# RCShield-v4.net
KiCad netlist of a schematic drawn in EAGLE
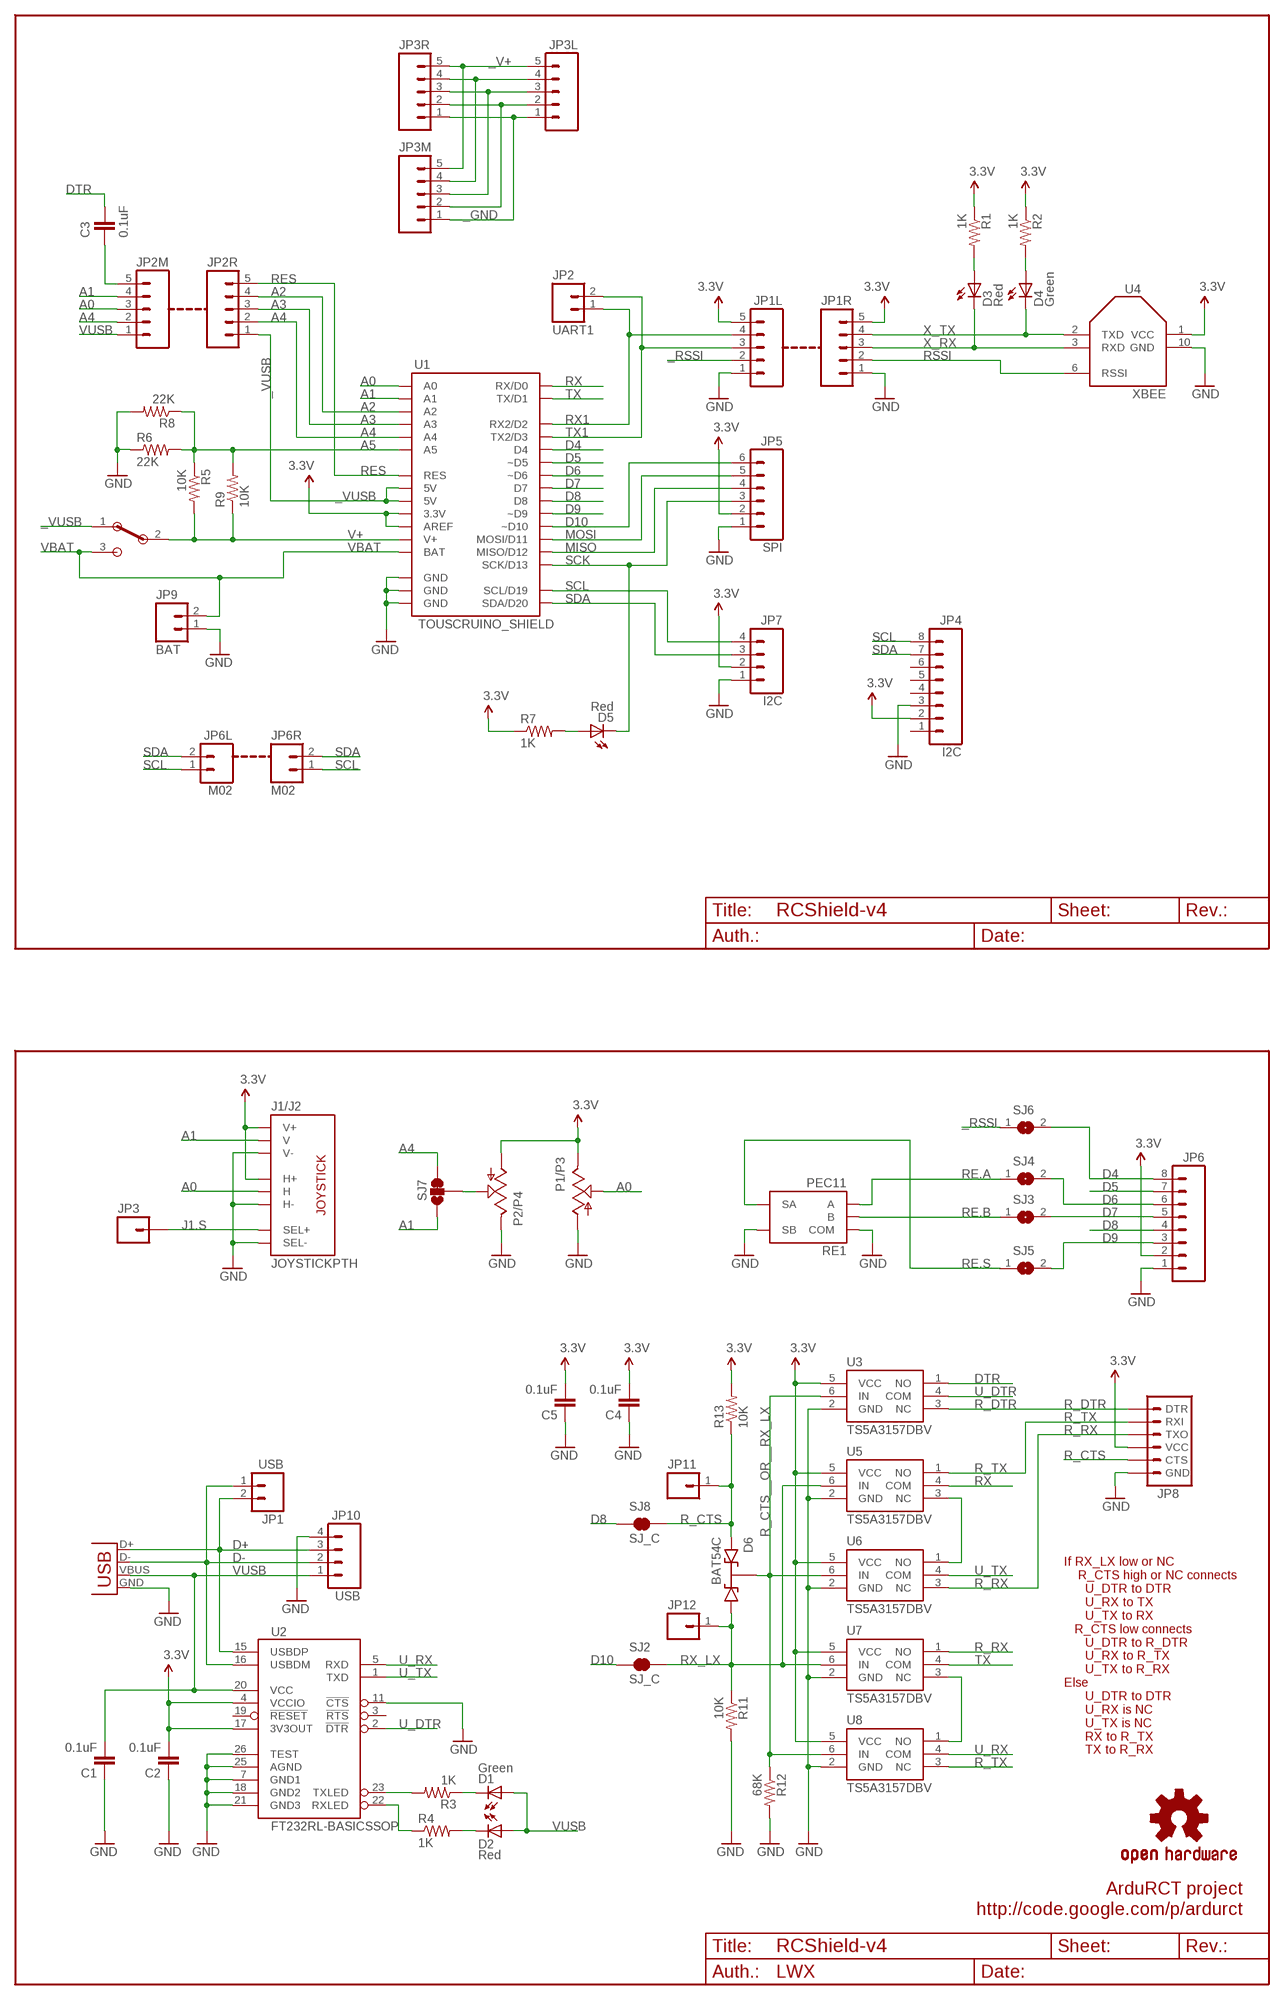
[diagram p0: schematic, sheet 1]

(export (version "E")
  (design (tool "Eeschema 10.0.6"))
  (components
    (comp (ref "C1")
      (value "0.1uF")
      (footprint "eagle-import:0805")
      (libsource (lib "eagle-import") (part "CAP0805"))
    )
    (comp (ref "C2")
      (value "0.1uF")
      (footprint "eagle-import:0805")
      (libsource (lib "eagle-import") (part "CAP0805"))
    )
    (comp (ref "C3")
      (value "0.1uF")
      (footprint "eagle-import:0805")
      (libsource (lib "eagle-import") (part "CAP0805"))
    )
    (comp (ref "C4")
      (value "0.1uF")
      (footprint "eagle-import:0805")
      (libsource (lib "eagle-import") (part "CAP0805"))
    )
    (comp (ref "C5")
      (value "0.1uF")
      (footprint "eagle-import:0805")
      (libsource (lib "eagle-import") (part "CAP0805"))
    )
    (comp (ref "D1")
      (value "Green")
      (footprint "eagle-import:LED")
      (libsource (lib "eagle-import") (part "LED"))
    )
    (comp (ref "D2")
      (value "Red")
      (footprint "eagle-import:LED")
      (libsource (lib "eagle-import") (part "LED"))
    )
    (comp (ref "D3")
      (value "Red")
      (footprint "eagle-import:LED")
      (libsource (lib "eagle-import") (part "LED"))
    )
    (comp (ref "D4")
      (value "Green")
      (footprint "eagle-import:LED")
      (libsource (lib "eagle-import") (part "LED"))
    )
    (comp (ref "D5")
      (value "Red")
      (footprint "eagle-import:LED")
      (libsource (lib "eagle-import") (part "LED"))
    )
    (comp (ref "D6")
      (value "BAT54C")
      (footprint "eagle-import:SOT23-3")
      (libsource (lib "eagle-import") (part "BAT54C"))
    )
    (comp (ref "J1/J2")
      (value "JOYSTICKPTH")
      (footprint "eagle-import:JOYSTICK")
      (libsource (lib "eagle-import") (part "JOYSTICKPTH"))
    )
    (comp (ref "JP1")
      (value "USB")
      (footprint "eagle-import:1X02")
      (libsource (lib "eagle-import") (part "M02"))
    )
    (comp (ref "JP1L")
      (value "M05")
      (footprint "eagle-import:2+3")
      (libsource (lib "eagle-import") (part "M05"))
    )
    (comp (ref "JP1R")
      (value "M05")
      (footprint "eagle-import:2+3")
      (libsource (lib "eagle-import") (part "M05"))
    )
    (comp (ref "JP2")
      (value "UART1")
      (footprint "eagle-import:1X02")
      (libsource (lib "eagle-import") (part "M02"))
    )
    (comp (ref "JP2M")
      (value "M05")
      (footprint "eagle-import:2+3")
      (libsource (lib "eagle-import") (part "M05"))
    )
    (comp (ref "JP2R")
      (value "M05")
      (footprint "eagle-import:2+3")
      (libsource (lib "eagle-import") (part "M05"))
    )
    (comp (ref "JP3")
      (value "M01PTH")
      (footprint "eagle-import:1X01")
      (libsource (lib "eagle-import") (part "M01PTH"))
    )
    (comp (ref "JP3L")
      (value "M05")
      (footprint "eagle-import:2+3")
      (libsource (lib "eagle-import") (part "M05"))
    )
    (comp (ref "JP3M")
      (value "M05")
      (footprint "eagle-import:2+3")
      (libsource (lib "eagle-import") (part "M05"))
    )
    (comp (ref "JP3R")
      (value "M05")
      (footprint "eagle-import:2+3")
      (libsource (lib "eagle-import") (part "M05"))
    )
    (comp (ref "JP4")
      (value "I2C")
      (footprint "eagle-import:1X08")
      (libsource (lib "eagle-import") (part "M08"))
    )
    (comp (ref "JP5")
      (value "SPI")
      (footprint "eagle-import:1X06")
      (libsource (lib "eagle-import") (part "M06SIP"))
    )
    (comp (ref "JP6")
      (value "M08")
      (footprint "eagle-import:1X08")
      (libsource (lib "eagle-import") (part "M08"))
    )
    (comp (ref "JP6L")
      (value "M02")
      (footprint "eagle-import:1X02")
      (libsource (lib "eagle-import") (part "M02"))
    )
    (comp (ref "JP6R")
      (value "M02")
      (footprint "eagle-import:1X02")
      (libsource (lib "eagle-import") (part "M02"))
    )
    (comp (ref "JP7")
      (value "I2C")
      (footprint "eagle-import:1X04")
      (libsource (lib "eagle-import") (part "M04"))
    )
    (comp (ref "JP8")
      (value "ARDUINO_SERIAL_PROGRAM")
      (footprint "eagle-import:1X06_F")
      (libsource (lib "eagle-import") (part "ARDUINO_SERIAL_PROGRAM"))
    )
    (comp (ref "JP9")
      (value "BAT")
      (footprint "eagle-import:1X02")
      (libsource (lib "eagle-import") (part "M02"))
    )
    (comp (ref "JP10")
      (value "USB")
      (footprint "eagle-import:1X04")
      (libsource (lib "eagle-import") (part "M04"))
    )
    (comp (ref "JP11")
      (value "M01SMALL")
      (footprint "eagle-import:1X01_S")
      (libsource (lib "eagle-import") (part "M01SMALL"))
    )
    (comp (ref "JP12")
      (value "M01SMALL")
      (footprint "eagle-import:1X01_S")
      (libsource (lib "eagle-import") (part "M01SMALL"))
    )
    (comp (ref "P1/P3")
      (value "POT")
      (footprint "eagle-import:ALPS_POT")
      (libsource (lib "eagle-import") (part "POT"))
    )
    (comp (ref "P2/P4")
      (value "POT")
      (footprint "eagle-import:ALPS_POT")
      (libsource (lib "eagle-import") (part "POT"))
    )
    (comp (ref "R1")
      (value "1K")
      (footprint "eagle-import:0805")
      (libsource (lib "eagle-import") (part "RESISTOR0805-RES"))
    )
    (comp (ref "R2")
      (value "1K")
      (footprint "eagle-import:0805")
      (libsource (lib "eagle-import") (part "RESISTOR0805-RES"))
    )
    (comp (ref "R3")
      (value "1K")
      (footprint "eagle-import:0805")
      (libsource (lib "eagle-import") (part "RESISTOR0805-RES"))
    )
    (comp (ref "R4")
      (value "1K")
      (footprint "eagle-import:0805")
      (libsource (lib "eagle-import") (part "RESISTOR0805-RES"))
    )
    (comp (ref "R5")
      (value "10K")
      (footprint "eagle-import:0805")
      (libsource (lib "eagle-import") (part "RESISTOR0805-RES"))
    )
    (comp (ref "R6")
      (value "22K")
      (footprint "eagle-import:0805")
      (libsource (lib "eagle-import") (part "RESISTOR0805-RES"))
    )
    (comp (ref "R7")
      (value "1K")
      (footprint "eagle-import:0805")
      (libsource (lib "eagle-import") (part "RESISTOR0805-RES"))
    )
    (comp (ref "R8")
      (value "22K")
      (footprint "eagle-import:0207_7")
      (libsource (lib "eagle-import") (part "R-US_0207/7"))
    )
    (comp (ref "R9")
      (value "10K")
      (footprint "eagle-import:0207_7")
      (libsource (lib "eagle-import") (part "R-US_0207/7"))
    )
    (comp (ref "R11")
      (value "10K")
      (footprint "eagle-import:0805")
      (libsource (lib "eagle-import") (part "RESISTOR0805-RES"))
    )
    (comp (ref "R12")
      (value "68K")
      (footprint "eagle-import:0805")
      (libsource (lib "eagle-import") (part "RESISTOR0805-RES"))
    )
    (comp (ref "R13")
      (value "10K")
      (footprint "eagle-import:0805")
      (libsource (lib "eagle-import") (part "RESISTOR0805-RES"))
    )
    (comp (ref "RE1")
      (value "PEC11")
      (footprint "eagle-import:PEC11")
      (libsource (lib "eagle-import") (part "PEC11"))
    )
    (comp (ref "S4")
      (value "EG1224")
      (footprint "eagle-import:EG1224")
      (libsource (lib "eagle-import") (part "EG1224"))
    )
    (comp (ref "SJ2")
      (value "SJ_C")
      (footprint "eagle-import:SJ_C")
      (libsource (lib "eagle-import") (part "SJ_C"))
    )
    (comp (ref "SJ3") (value "SJ") (footprint "eagle-import:SJ") (libsource (lib "eagle-import") (part "SJ")))
    (comp (ref "SJ4") (value "SJ") (footprint "eagle-import:SJ") (libsource (lib "eagle-import") (part "SJ")))
    (comp (ref "SJ5") (value "SJ") (footprint "eagle-import:SJ") (libsource (lib "eagle-import") (part "SJ")))
    (comp (ref "SJ6") (value "SJ") (footprint "eagle-import:SJ") (libsource (lib "eagle-import") (part "SJ")))
    (comp (ref "SJ7")
      (value "SJ_2WAYS_1-2W")
      (footprint "eagle-import:SJ_2WAYS_1-2")
      (libsource (lib "eagle-import") (part "SJ_2WAYS_1-2W"))
    )
    (comp (ref "SJ8")
      (value "SJ_C")
      (footprint "eagle-import:SJ_C")
      (libsource (lib "eagle-import") (part "SJ_C"))
    )
    (comp (ref "U$1")
      (value "OSHW-LOGOM")
      (footprint "eagle-import:OSHW-LOGO-M")
      (libsource (lib "eagle-import") (part "OSHW-LOGOM"))
    )
    (comp (ref "U1")
      (value "TOUSCRUINO_SHIELD")
      (footprint "eagle-import:TOUSCRUINO_SHIELD_SPLIT")
      (libsource (lib "eagle-import") (part "TOUSCRUINO_SHIELDSPLIT"))
    )
    (comp (ref "U2")
      (value "FT232RL-BASICSSOP")
      (footprint "eagle-import:SSOP28DB")
      (libsource (lib "eagle-import") (part "FT232RL-BASICSSOP"))
    )
    (comp (ref "U3")
      (value "TS5A3157DBV")
      (footprint "eagle-import:SOT23-6")
      (libsource (lib "eagle-import") (part "TS5A3157DBV"))
    )
    (comp (ref "U4")
      (value "XBEE")
      (footprint "eagle-import:XBEE-SMD")
      (libsource (lib "eagle-import") (part "XBEE-RSSI"))
    )
    (comp (ref "U5")
      (value "TS5A3157DBV")
      (footprint "eagle-import:SOT23-6")
      (libsource (lib "eagle-import") (part "TS5A3157DBV"))
    )
    (comp (ref "U6")
      (value "TS5A3157DBV")
      (footprint "eagle-import:SOT23-6")
      (libsource (lib "eagle-import") (part "TS5A3157DBV"))
    )
    (comp (ref "U7")
      (value "TS5A3157DBV")
      (footprint "eagle-import:SOT23-6")
      (libsource (lib "eagle-import") (part "TS5A3157DBV"))
    )
    (comp (ref "U8")
      (value "TS5A3157DBV")
      (footprint "eagle-import:SOT23-6")
      (libsource (lib "eagle-import") (part "TS5A3157DBV"))
    )
    (comp (ref "X1")
      (value "USB")
      (footprint "eagle-import:USB-MICROB")
      (libsource (lib "eagle-import") (part "USB"))
    )
  )
  (nets
    (net (code "1") (name "/A0") (class "Default")
      (node (ref "J1/J2") (pin "H2") (pinfunction "H_H2") (pintype "bidirectional"))
      (node (ref "JP2M") (pin "3") (pinfunction "3_3") (pintype "passive"))
      (node (ref "P1/P3") (pin "P$2") (pinfunction "S_P$2") (pintype "passive"))
      (node (ref "U1") (pin "A0") (pinfunction "A0_A0") (pintype "bidirectional"))
    )
    (net (code "2") (name "/A1") (class "Default")
      (node (ref "J1/J2") (pin "V2") (pinfunction "V_V2") (pintype "bidirectional"))
      (node (ref "JP2M") (pin "4") (pinfunction "4_4") (pintype "passive"))
      (node (ref "SJ7") (pin "3") (pinfunction "3_3") (pintype "passive"))
      (node (ref "U1") (pin "A1") (pinfunction "A1_A1") (pintype "bidirectional"))
    )
    (net (code "3") (name "/A2") (class "Default")
      (node (ref "JP2R") (pin "4") (pinfunction "4_4") (pintype "passive"))
      (node (ref "U1") (pin "A2") (pinfunction "A2_A2") (pintype "bidirectional"))
    )
    (net (code "4") (name "/A3") (class "Default")
      (node (ref "JP2R") (pin "3") (pinfunction "3_3") (pintype "passive"))
      (node (ref "U1") (pin "A3") (pinfunction "A3_A3") (pintype "bidirectional"))
    )
    (net (code "5") (name "/A4") (class "Default")
      (node (ref "JP2M") (pin "2") (pinfunction "2_2") (pintype "passive"))
      (node (ref "JP2R") (pin "2") (pinfunction "2_2") (pintype "passive"))
      (node (ref "SJ7") (pin "1") (pinfunction "1_1") (pintype "passive"))
      (node (ref "U1") (pin "A4") (pinfunction "A4_A4") (pintype "bidirectional"))
    )
    (net (code "6") (name "/A5") (class "Default")
      (node (ref "R5") (pin "1") (pinfunction "1_1") (pintype "passive"))
      (node (ref "R6") (pin "2") (pinfunction "2_2") (pintype "passive"))
      (node (ref "R8") (pin "1") (pinfunction "1_1") (pintype "passive"))
      (node (ref "R9") (pin "2") (pinfunction "2_2") (pintype "passive"))
      (node (ref "U1") (pin "A5") (pinfunction "A5_A5") (pintype "bidirectional"))
    )
    (net (code "7") (name "/D+") (class "Default")
      (node (ref "JP1") (pin "2") (pinfunction "2_2") (pintype "passive"))
      (node (ref "JP10") (pin "3") (pinfunction "3_3") (pintype "passive"))
      (node (ref "U2") (pin "15") (pinfunction "USBDP_15") (pintype "bidirectional"))
      (node (ref "X1") (pin "D+") (pinfunction "D+_D+") (pintype "bidirectional"))
    )
    (net (code "8") (name "/D-") (class "Default")
      (node (ref "JP1") (pin "1") (pinfunction "1_1") (pintype "passive"))
      (node (ref "JP10") (pin "2") (pinfunction "2_2") (pintype "passive"))
      (node (ref "U2") (pin "16") (pinfunction "USBDM_16") (pintype "bidirectional"))
      (node (ref "X1") (pin "D-") (pinfunction "D-_D-") (pintype "bidirectional"))
    )
    (net (code "9") (name "/D4") (class "Default")
      (node (ref "JP6") (pin "8") (pinfunction "8_8") (pintype "passive"))
      (node (ref "SJ6") (pin "2") (pinfunction "2_2") (pintype "passive"))
      (node (ref "U1") (pin "D4") (pinfunction "D4_D4") (pintype "bidirectional"))
    )
    (net (code "10") (name "/D5") (class "Default")
      (node (ref "JP6") (pin "7") (pinfunction "7_7") (pintype "passive"))
      (node (ref "U1") (pin "D5") (pinfunction "~{D5}_D5") (pintype "bidirectional"))
    )
    (net (code "11") (name "/D6") (class "Default")
      (node (ref "JP6") (pin "6") (pinfunction "6_6") (pintype "passive"))
      (node (ref "SJ4") (pin "2") (pinfunction "2_2") (pintype "passive"))
      (node (ref "U1") (pin "D6") (pinfunction "~{D6}_D6") (pintype "bidirectional"))
    )
    (net (code "12") (name "/D7") (class "Default")
      (node (ref "JP6") (pin "5") (pinfunction "5_5") (pintype "passive"))
      (node (ref "SJ3") (pin "2") (pinfunction "2_2") (pintype "passive"))
      (node (ref "U1") (pin "D7") (pinfunction "D7_D7") (pintype "bidirectional"))
    )
    (net (code "13") (name "/D8") (class "Default")
      (node (ref "JP6") (pin "4") (pinfunction "4_4") (pintype "passive"))
      (node (ref "SJ8") (pin "1") (pinfunction "1_1") (pintype "passive"))
      (node (ref "U1") (pin "D8") (pinfunction "D8_D8") (pintype "bidirectional"))
    )
    (net (code "14") (name "/D9") (class "Default")
      (node (ref "JP6") (pin "3") (pinfunction "3_3") (pintype "passive"))
      (node (ref "SJ5") (pin "2") (pinfunction "2_2") (pintype "passive"))
      (node (ref "U1") (pin "D9") (pinfunction "~{D9}_D9") (pintype "bidirectional"))
    )
    (net (code "15") (name "/D10") (class "Default")
      (node (ref "JP5") (pin "6") (pinfunction "6_6") (pintype "passive"))
      (node (ref "SJ2") (pin "1") (pinfunction "1_1") (pintype "passive"))
      (node (ref "U1") (pin "D10") (pinfunction "~{D10}_D10") (pintype "bidirectional"))
    )
    (net (code "16") (name "/DTR") (class "Default")
      (node (ref "C3") (pin "1") (pinfunction "1_1") (pintype "passive"))
      (node (ref "U3") (pin "1") (pinfunction "NO_1") (pintype "bidirectional"))
    )
    (net (code "17") (name "/J1.S") (class "Default")
      (node (ref "J1/J2") (pin "B1A") (pinfunction "SEL+_B1A") (pintype "bidirectional"))
      (node (ref "JP3") (pin "1") (pinfunction "1_1") (pintype "passive"))
    )
    (net (code "18") (name "/MISO") (class "Default")
      (node (ref "JP5") (pin "4") (pinfunction "4_4") (pintype "passive"))
      (node (ref "U1") (pin "D12") (pinfunction "MISO/D12_D12") (pintype "bidirectional"))
    )
    (net (code "19") (name "/MOSI") (class "Default")
      (node (ref "JP5") (pin "5") (pinfunction "5_5") (pintype "passive"))
      (node (ref "U1") (pin "D11") (pinfunction "MOSI/D11_D11") (pintype "bidirectional"))
    )
    (net (code "20") (name "/RE.A") (class "Default")
      (node (ref "RE1") (pin "A") (pinfunction "A_A") (pintype "bidirectional"))
      (node (ref "SJ4") (pin "1") (pinfunction "1_1") (pintype "passive"))
    )
    (net (code "21") (name "/RE.B") (class "Default")
      (node (ref "RE1") (pin "B") (pinfunction "B_B") (pintype "bidirectional"))
      (node (ref "SJ3") (pin "1") (pinfunction "1_1") (pintype "passive"))
    )
    (net (code "22") (name "/RE.S") (class "Default")
      (node (ref "RE1") (pin "S1") (pinfunction "SA_S1") (pintype "bidirectional"))
      (node (ref "SJ5") (pin "1") (pinfunction "1_1") (pintype "passive"))
    )
    (net (code "23") (name "/RES") (class "Default")
      (node (ref "JP2R") (pin "5") (pinfunction "5_5") (pintype "passive"))
      (node (ref "U1") (pin "RES") (pinfunction "RES_RES") (pintype "bidirectional"))
    )
    (net (code "24") (name "/RSSI") (class "Default")
      (node (ref "JP1R") (pin "2") (pinfunction "2_2") (pintype "passive"))
      (node (ref "U4") (pin "6") (pinfunction "RSSI_6") (pintype "bidirectional"))
    )
    (net (code "25") (name "/RX") (class "Default")
      (node (ref "U1") (pin "RX") (pinfunction "RX/D0_RX") (pintype "bidirectional"))
      (node (ref "U5") (pin "4") (pinfunction "COM_4") (pintype "bidirectional"))
    )
    (net (code "26") (name "/RX1") (class "Default")
      (node (ref "JP1L") (pin "4") (pinfunction "4_4") (pintype "passive"))
      (node (ref "JP2") (pin "1") (pinfunction "1_1") (pintype "passive"))
      (node (ref "U1") (pin "D2") (pinfunction "RX2/D2_D2") (pintype "bidirectional"))
    )
    (net (code "27") (name "/RX_LX") (class "Default")
      (node (ref "D6") (pin "1") (pinfunction "A1_1") (pintype "bidirectional"))
      (node (ref "JP12") (pin "1") (pinfunction "1_1") (pintype "passive"))
      (node (ref "R11") (pin "1") (pinfunction "1_1") (pintype "passive"))
      (node (ref "SJ2") (pin "2") (pinfunction "2_2") (pintype "passive"))
      (node (ref "U5") (pin "6") (pinfunction "IN_6") (pintype "bidirectional"))
      (node (ref "U7") (pin "6") (pinfunction "IN_6") (pintype "bidirectional"))
    )
    (net (code "28") (name "/R_CTS") (class "Default")
      (node (ref "D6") (pin "2") (pinfunction "A2_2") (pintype "bidirectional"))
      (node (ref "JP11") (pin "1") (pinfunction "1_1") (pintype "passive"))
      (node (ref "JP8") (pin "5") (pinfunction "CTS_5") (pintype "passive"))
      (node (ref "R13") (pin "1") (pinfunction "1_1") (pintype "passive"))
      (node (ref "SJ8") (pin "2") (pinfunction "2_2") (pintype "passive"))
    )
    (net (code "29") (name "/R_CTS__OR__RX_LX") (class "Default")
      (node (ref "D6") (pin "3") (pinfunction "K_3") (pintype "bidirectional"))
      (node (ref "R12") (pin "1") (pinfunction "1_1") (pintype "passive"))
      (node (ref "U3") (pin "6") (pinfunction "IN_6") (pintype "bidirectional"))
      (node (ref "U6") (pin "6") (pinfunction "IN_6") (pintype "bidirectional"))
      (node (ref "U8") (pin "6") (pinfunction "IN_6") (pintype "bidirectional"))
    )
    (net (code "30") (name "/R_DTR") (class "Default")
      (node (ref "JP8") (pin "1") (pinfunction "DTR_1") (pintype "passive"))
      (node (ref "U3") (pin "3") (pinfunction "NC_3") (pintype "bidirectional"))
    )
    (net (code "31") (name "/R_RX") (class "Default")
      (node (ref "JP8") (pin "3") (pinfunction "TXO_3") (pintype "passive"))
      (node (ref "U6") (pin "3") (pinfunction "NC_3") (pintype "bidirectional"))
      (node (ref "U7") (pin "1") (pinfunction "NO_1") (pintype "bidirectional"))
    )
    (net (code "32") (name "/R_TX") (class "Default")
      (node (ref "JP8") (pin "2") (pinfunction "RXI_2") (pintype "passive"))
      (node (ref "U5") (pin "1") (pinfunction "NO_1") (pintype "bidirectional"))
      (node (ref "U8") (pin "3") (pinfunction "NC_3") (pintype "bidirectional"))
    )
    (net (code "33") (name "/SCK") (class "Default")
      (node (ref "D5") (pin "C1") (pinfunction "C_C1") (pintype "passive"))
      (node (ref "JP5") (pin "3") (pinfunction "3_3") (pintype "passive"))
      (node (ref "U1") (pin "D13") (pinfunction "SCK/D13_D13") (pintype "bidirectional"))
    )
    (net (code "34") (name "/SCL") (class "Default")
      (node (ref "JP4") (pin "8") (pinfunction "8_8") (pintype "passive"))
      (node (ref "JP6L") (pin "1") (pinfunction "1_1") (pintype "passive"))
      (node (ref "JP6R") (pin "1") (pinfunction "1_1") (pintype "passive"))
      (node (ref "JP7") (pin "4") (pinfunction "4_4") (pintype "passive"))
      (node (ref "U1") (pin "SCL") (pinfunction "SCL/D19_SCL") (pintype "bidirectional"))
    )
    (net (code "35") (name "/SDA") (class "Default")
      (node (ref "JP4") (pin "7") (pinfunction "7_7") (pintype "passive"))
      (node (ref "JP6L") (pin "2") (pinfunction "2_2") (pintype "passive"))
      (node (ref "JP6R") (pin "2") (pinfunction "2_2") (pintype "passive"))
      (node (ref "JP7") (pin "3") (pinfunction "3_3") (pintype "passive"))
      (node (ref "U1") (pin "SDA") (pinfunction "SDA/D20_SDA") (pintype "bidirectional"))
    )
    (net (code "36") (name "/TX") (class "Default")
      (node (ref "U1") (pin "TX") (pinfunction "TX/D1_TX") (pintype "bidirectional"))
      (node (ref "U7") (pin "4") (pinfunction "COM_4") (pintype "bidirectional"))
    )
    (net (code "37") (name "/TX1") (class "Default")
      (node (ref "JP1L") (pin "3") (pinfunction "3_3") (pintype "passive"))
      (node (ref "JP2") (pin "2") (pinfunction "2_2") (pintype "passive"))
      (node (ref "U1") (pin "D3") (pinfunction "TX2/D3_D3") (pintype "bidirectional"))
    )
    (net (code "38") (name "/U_DTR") (class "Default")
      (node (ref "U2") (pin "2") (pinfunction "~{DTR}_2") (pintype "bidirectional"))
      (node (ref "U3") (pin "4") (pinfunction "COM_4") (pintype "bidirectional"))
    )
    (net (code "39") (name "/U_RX") (class "Default")
      (node (ref "U2") (pin "5") (pinfunction "RXD_5") (pintype "input"))
      (node (ref "U8") (pin "4") (pinfunction "COM_4") (pintype "bidirectional"))
    )
    (net (code "40") (name "/U_TX") (class "Default")
      (node (ref "U2") (pin "1") (pinfunction "TXD_1") (pintype "output"))
      (node (ref "U6") (pin "4") (pinfunction "COM_4") (pintype "bidirectional"))
    )
    (net (code "41") (name "/V+") (class "Default")
      (node (ref "R5") (pin "2") (pinfunction "2_2") (pintype "passive"))
      (node (ref "R9") (pin "1") (pinfunction "1_1") (pintype "passive"))
      (node (ref "S4") (pin "2") (pinfunction "2_2") (pintype "bidirectional"))
      (node (ref "U1") (pin "V+") (pinfunction "V+_V+") (pintype "bidirectional"))
    )
    (net (code "42") (name "/VBAT") (class "Default")
      (node (ref "JP9") (pin "2") (pinfunction "2_2") (pintype "passive"))
      (node (ref "S4") (pin "3") (pinfunction "3_3") (pintype "bidirectional"))
      (node (ref "U1") (pin "BAT") (pinfunction "BAT_BAT") (pintype "bidirectional"))
    )
    (net (code "43") (name "/VUSB") (class "Default")
      (node (ref "C1") (pin "2") (pinfunction "2_2") (pintype "passive"))
      (node (ref "D1") (pin "A1") (pinfunction "A_A1") (pintype "passive"))
      (node (ref "D2") (pin "A1") (pinfunction "A_A1") (pintype "passive"))
      (node (ref "JP10") (pin "1") (pinfunction "1_1") (pintype "passive"))
      (node (ref "JP2M") (pin "1") (pinfunction "1_1") (pintype "passive"))
      (node (ref "U2") (pin "20") (pinfunction "VCC_20") (pintype "bidirectional"))
      (node (ref "X1") (pin "VBUS") (pinfunction "VBUS_VBUS") (pintype "bidirectional"))
    )
    (net (code "44") (name "/X_RX") (class "Default")
      (node (ref "D3") (pin "C1") (pinfunction "C_C1") (pintype "passive"))
      (node (ref "JP1R") (pin "3") (pinfunction "3_3") (pintype "passive"))
      (node (ref "U4") (pin "3") (pinfunction "RXD_3") (pintype "bidirectional"))
    )
    (net (code "45") (name "/X_TX") (class "Default")
      (node (ref "D4") (pin "C1") (pinfunction "C_C1") (pintype "passive"))
      (node (ref "JP1R") (pin "4") (pinfunction "4_4") (pintype "passive"))
      (node (ref "U4") (pin "2") (pinfunction "TXD_2") (pintype "bidirectional"))
    )
    (net (code "46") (name "/_GND") (class "Default")
      (node (ref "JP3L") (pin "1") (pinfunction "1_1") (pintype "passive"))
      (node (ref "JP3M") (pin "1") (pinfunction "1_1") (pintype "passive"))
      (node (ref "JP3R") (pin "1") (pinfunction "1_1") (pintype "passive"))
    )
    (net (code "47") (name "/_RSSI") (class "Default")
      (node (ref "JP1L") (pin "2") (pinfunction "2_2") (pintype "passive"))
      (node (ref "SJ6") (pin "1") (pinfunction "1_1") (pintype "passive"))
    )
    (net (code "48") (name "/_V+") (class "Default")
      (node (ref "JP3L") (pin "5") (pinfunction "5_5") (pintype "passive"))
      (node (ref "JP3M") (pin "5") (pinfunction "5_5") (pintype "passive"))
      (node (ref "JP3R") (pin "5") (pinfunction "5_5") (pintype "passive"))
    )
    (net (code "49") (name "/_VUSB") (class "Default")
      (node (ref "JP2R") (pin "1") (pinfunction "1_1") (pintype "passive"))
      (node (ref "S4") (pin "1") (pinfunction "1_1") (pintype "bidirectional"))
      (node (ref "U1") (pin "5V@0") (pinfunction "5V_5V@0") (pintype "bidirectional"))
      (node (ref "U1") (pin "5V@1") (pinfunction "5V_5V@1") (pintype "bidirectional"))
    )
    (net (code "50") (name "3.3V") (class "Default")
      (node (ref "C2") (pin "2") (pinfunction "2_2") (pintype "passive"))
      (node (ref "C4") (pin "2") (pinfunction "2_2") (pintype "passive"))
      (node (ref "C5") (pin "2") (pinfunction "2_2") (pintype "passive"))
      (node (ref "J1/J2") (pin "H1") (pinfunction "H+_H1") (pintype "bidirectional"))
      (node (ref "J1/J2") (pin "V1") (pinfunction "V+_V1") (pintype "bidirectional"))
      (node (ref "JP1L") (pin "5") (pinfunction "5_5") (pintype "passive"))
      (node (ref "JP1R") (pin "5") (pinfunction "5_5") (pintype "passive"))
      (node (ref "JP4") (pin "2") (pinfunction "2_2") (pintype "passive"))
      (node (ref "JP5") (pin "2") (pinfunction "2_2") (pintype "passive"))
      (node (ref "JP6") (pin "2") (pinfunction "2_2") (pintype "passive"))
      (node (ref "JP7") (pin "2") (pinfunction "2_2") (pintype "passive"))
      (node (ref "JP8") (pin "4") (pinfunction "VCC_4") (pintype "passive"))
      (node (ref "P1/P3") (pin "P$1") (pinfunction "E_P$1") (pintype "passive"))
      (node (ref "P2/P4") (pin "P$3") (pinfunction "A_P$3") (pintype "passive"))
      (node (ref "R1") (pin "1") (pinfunction "1_1") (pintype "passive"))
      (node (ref "R13") (pin "2") (pinfunction "2_2") (pintype "passive"))
      (node (ref "R2") (pin "1") (pinfunction "1_1") (pintype "passive"))
      (node (ref "R7") (pin "1") (pinfunction "1_1") (pintype "passive"))
      (node (ref "U1") (pin "3.3V") (pinfunction "3.3V_3.3V") (pintype "bidirectional"))
      (node (ref "U1") (pin "AREF") (pinfunction "AREF_AREF") (pintype "bidirectional"))
      (node (ref "U2") (pin "17") (pinfunction "3V3OUT_17") (pintype "output"))
      (node (ref "U2") (pin "4") (pinfunction "VCCIO_4") (pintype "bidirectional"))
      (node (ref "U3") (pin "5") (pinfunction "VCC_5") (pintype "bidirectional"))
      (node (ref "U4") (pin "1") (pinfunction "VCC_1") (pintype "bidirectional"))
      (node (ref "U5") (pin "5") (pinfunction "VCC_5") (pintype "bidirectional"))
      (node (ref "U6") (pin "5") (pinfunction "VCC_5") (pintype "bidirectional"))
      (node (ref "U7") (pin "5") (pinfunction "VCC_5") (pintype "bidirectional"))
      (node (ref "U8") (pin "5") (pinfunction "VCC_5") (pintype "bidirectional"))
    )
    (net (code "51") (name "GND") (class "Default")
      (node (ref "C1") (pin "1") (pinfunction "1_1") (pintype "passive"))
      (node (ref "C2") (pin "1") (pinfunction "1_1") (pintype "passive"))
      (node (ref "C4") (pin "1") (pinfunction "1_1") (pintype "passive"))
      (node (ref "C5") (pin "1") (pinfunction "1_1") (pintype "passive"))
      (node (ref "J1/J2") (pin "B2A") (pinfunction "SEL-_B2A") (pintype "bidirectional"))
      (node (ref "J1/J2") (pin "H3") (pinfunction "H-_H3") (pintype "bidirectional"))
      (node (ref "J1/J2") (pin "V3") (pinfunction "V-_V3") (pintype "bidirectional"))
      (node (ref "JP10") (pin "4") (pinfunction "4_4") (pintype "passive"))
      (node (ref "JP1L") (pin "1") (pinfunction "1_1") (pintype "passive"))
      (node (ref "JP1R") (pin "1") (pinfunction "1_1") (pintype "passive"))
      (node (ref "JP4") (pin "3") (pinfunction "3_3") (pintype "passive"))
      (node (ref "JP5") (pin "1") (pinfunction "1_1") (pintype "passive"))
      (node (ref "JP6") (pin "1") (pinfunction "1_1") (pintype "passive"))
      (node (ref "JP7") (pin "1") (pinfunction "1_1") (pintype "passive"))
      (node (ref "JP8") (pin "6") (pinfunction "GND_6") (pintype "passive"))
      (node (ref "JP9") (pin "1") (pinfunction "1_1") (pintype "passive"))
      (node (ref "P1/P3") (pin "P$3") (pinfunction "A_P$3") (pintype "passive"))
      (node (ref "P2/P4") (pin "P$1") (pinfunction "E_P$1") (pintype "passive"))
      (node (ref "R11") (pin "2") (pinfunction "2_2") (pintype "passive"))
      (node (ref "R12") (pin "2") (pinfunction "2_2") (pintype "passive"))
      (node (ref "R6") (pin "1") (pinfunction "1_1") (pintype "passive"))
      (node (ref "R8") (pin "2") (pinfunction "2_2") (pintype "passive"))
      (node (ref "RE1") (pin "C") (pinfunction "COM_C") (pintype "bidirectional"))
      (node (ref "RE1") (pin "S2") (pinfunction "SB_S2") (pintype "bidirectional"))
      (node (ref "U1") (pin "GND@0") (pinfunction "GND_GND@0") (pintype "bidirectional"))
      (node (ref "U1") (pin "GND@1") (pinfunction "GND_GND@1") (pintype "bidirectional"))
      (node (ref "U1") (pin "GND@2") (pinfunction "GND_GND@2") (pintype "bidirectional"))
      (node (ref "U2") (pin "11") (pinfunction "~{CTS}_11") (pintype "bidirectional"))
      (node (ref "U2") (pin "18") (pinfunction "GND2_18") (pintype "bidirectional"))
      (node (ref "U2") (pin "21") (pinfunction "GND3_21") (pintype "bidirectional"))
      (node (ref "U2") (pin "25") (pinfunction "AGND_25") (pintype "bidirectional"))
      (node (ref "U2") (pin "26") (pinfunction "TEST_26") (pintype "input"))
      (node (ref "U2") (pin "7") (pinfunction "GND1_7") (pintype "bidirectional"))
      (node (ref "U3") (pin "2") (pinfunction "GND_2") (pintype "bidirectional"))
      (node (ref "U4") (pin "10") (pinfunction "GND_10") (pintype "bidirectional"))
      (node (ref "U5") (pin "2") (pinfunction "GND_2") (pintype "bidirectional"))
      (node (ref "U6") (pin "2") (pinfunction "GND_2") (pintype "bidirectional"))
      (node (ref "U7") (pin "2") (pinfunction "GND_2") (pintype "bidirectional"))
      (node (ref "U8") (pin "2") (pinfunction "GND_2") (pintype "bidirectional"))
      (node (ref "X1") (pin "GND") (pinfunction "GND_GND") (pintype "bidirectional"))
    )
    (net (code "52") (name "Net-(C3-Pad2)") (class "Default")
      (node (ref "C3") (pin "2") (pinfunction "2_2") (pintype "passive"))
      (node (ref "JP2M") (pin "5") (pinfunction "5_5") (pintype "passive"))
    )
    (net (code "53") (name "Net-(D1-C)") (class "Default")
      (node (ref "D1") (pin "C1") (pinfunction "C_C1") (pintype "passive"))
      (node (ref "R3") (pin "1") (pinfunction "1_1") (pintype "passive"))
    )
    (net (code "54") (name "Net-(D2-C)") (class "Default")
      (node (ref "D2") (pin "C1") (pinfunction "C_C1") (pintype "passive"))
      (node (ref "R4") (pin "2") (pinfunction "2_2") (pintype "passive"))
    )
    (net (code "55") (name "Net-(D3-A)") (class "Default")
      (node (ref "D3") (pin "A1") (pinfunction "A_A1") (pintype "passive"))
      (node (ref "R1") (pin "2") (pinfunction "2_2") (pintype "passive"))
    )
    (net (code "56") (name "Net-(D4-A)") (class "Default")
      (node (ref "D4") (pin "A1") (pinfunction "A_A1") (pintype "passive"))
      (node (ref "R2") (pin "2") (pinfunction "2_2") (pintype "passive"))
    )
    (net (code "57") (name "Net-(D5-A)") (class "Default")
      (node (ref "D5") (pin "A1") (pinfunction "A_A1") (pintype "passive"))
      (node (ref "R7") (pin "2") (pinfunction "2_2") (pintype "passive"))
    )
    (net (code "58") (name "Net-(JP3L-Pad2)") (class "Default")
      (node (ref "JP3L") (pin "2") (pinfunction "2_2") (pintype "passive"))
      (node (ref "JP3M") (pin "2") (pinfunction "2_2") (pintype "passive"))
      (node (ref "JP3R") (pin "2") (pinfunction "2_2") (pintype "passive"))
    )
    (net (code "59") (name "Net-(JP3L-Pad3)") (class "Default")
      (node (ref "JP3L") (pin "3") (pinfunction "3_3") (pintype "passive"))
      (node (ref "JP3M") (pin "3") (pinfunction "3_3") (pintype "passive"))
      (node (ref "JP3R") (pin "3") (pinfunction "3_3") (pintype "passive"))
    )
    (net (code "60") (name "Net-(JP3L-Pad4)") (class "Default")
      (node (ref "JP3L") (pin "4") (pinfunction "4_4") (pintype "passive"))
      (node (ref "JP3M") (pin "4") (pinfunction "4_4") (pintype "passive"))
      (node (ref "JP3R") (pin "4") (pinfunction "4_4") (pintype "passive"))
    )
    (net (code "61") (name "Net-(P2/P4-S)") (class "Default")
      (node (ref "P2/P4") (pin "P$2") (pinfunction "S_P$2") (pintype "passive"))
      (node (ref "SJ7") (pin "2") (pinfunction "2_2") (pintype "passive"))
    )
    (net (code "62") (name "Net-(U2-RXLED)") (class "Default")
      (node (ref "R4") (pin "1") (pinfunction "1_1") (pintype "passive"))
      (node (ref "U2") (pin "22") (pinfunction "RXLED_22") (pintype "bidirectional"))
    )
    (net (code "63") (name "Net-(U2-TXLED)") (class "Default")
      (node (ref "R3") (pin "2") (pinfunction "2_2") (pintype "passive"))
      (node (ref "U2") (pin "23") (pinfunction "TXLED_23") (pintype "bidirectional"))
    )
    (net (code "64") (name "Net-(U5-NC)") (class "Default")
      (node (ref "U5") (pin "3") (pinfunction "NC_3") (pintype "bidirectional"))
      (node (ref "U6") (pin "1") (pinfunction "NO_1") (pintype "bidirectional"))
    )
    (net (code "65") (name "Net-(U7-NC)") (class "Default")
      (node (ref "U7") (pin "3") (pinfunction "NC_3") (pintype "bidirectional"))
      (node (ref "U8") (pin "1") (pinfunction "NO_1") (pintype "bidirectional"))
    )
    (net (code "66") (name "unconnected-(JP4-Pad1)") (class "Default")
      (node (ref "JP4") (pin "1") (pinfunction "1_1") (pintype "passive"))
    )
    (net (code "67") (name "unconnected-(JP4-Pad4)") (class "Default")
      (node (ref "JP4") (pin "4") (pinfunction "4_4") (pintype "passive"))
    )
    (net (code "68") (name "unconnected-(JP4-Pad5)") (class "Default")
      (node (ref "JP4") (pin "5") (pinfunction "5_5") (pintype "passive"))
    )
    (net (code "69") (name "unconnected-(JP4-Pad6)") (class "Default")
      (node (ref "JP4") (pin "6") (pinfunction "6_6") (pintype "passive"))
    )
    (net (code "70") (name "unconnected-(U2-~{RESET}-Pad19)") (class "Default")
      (node (ref "U2") (pin "19") (pinfunction "~{RESET}_19") (pintype "bidirectional"))
    )
    (net (code "71") (name "unconnected-(U2-~{RTS}-Pad3)") (class "Default")
      (node (ref "U2") (pin "3") (pinfunction "~{RTS}_3") (pintype "bidirectional"))
    )
  )
)
